# Datalogging.net
KiCad netlist of a schematic drawn in Altium Designer
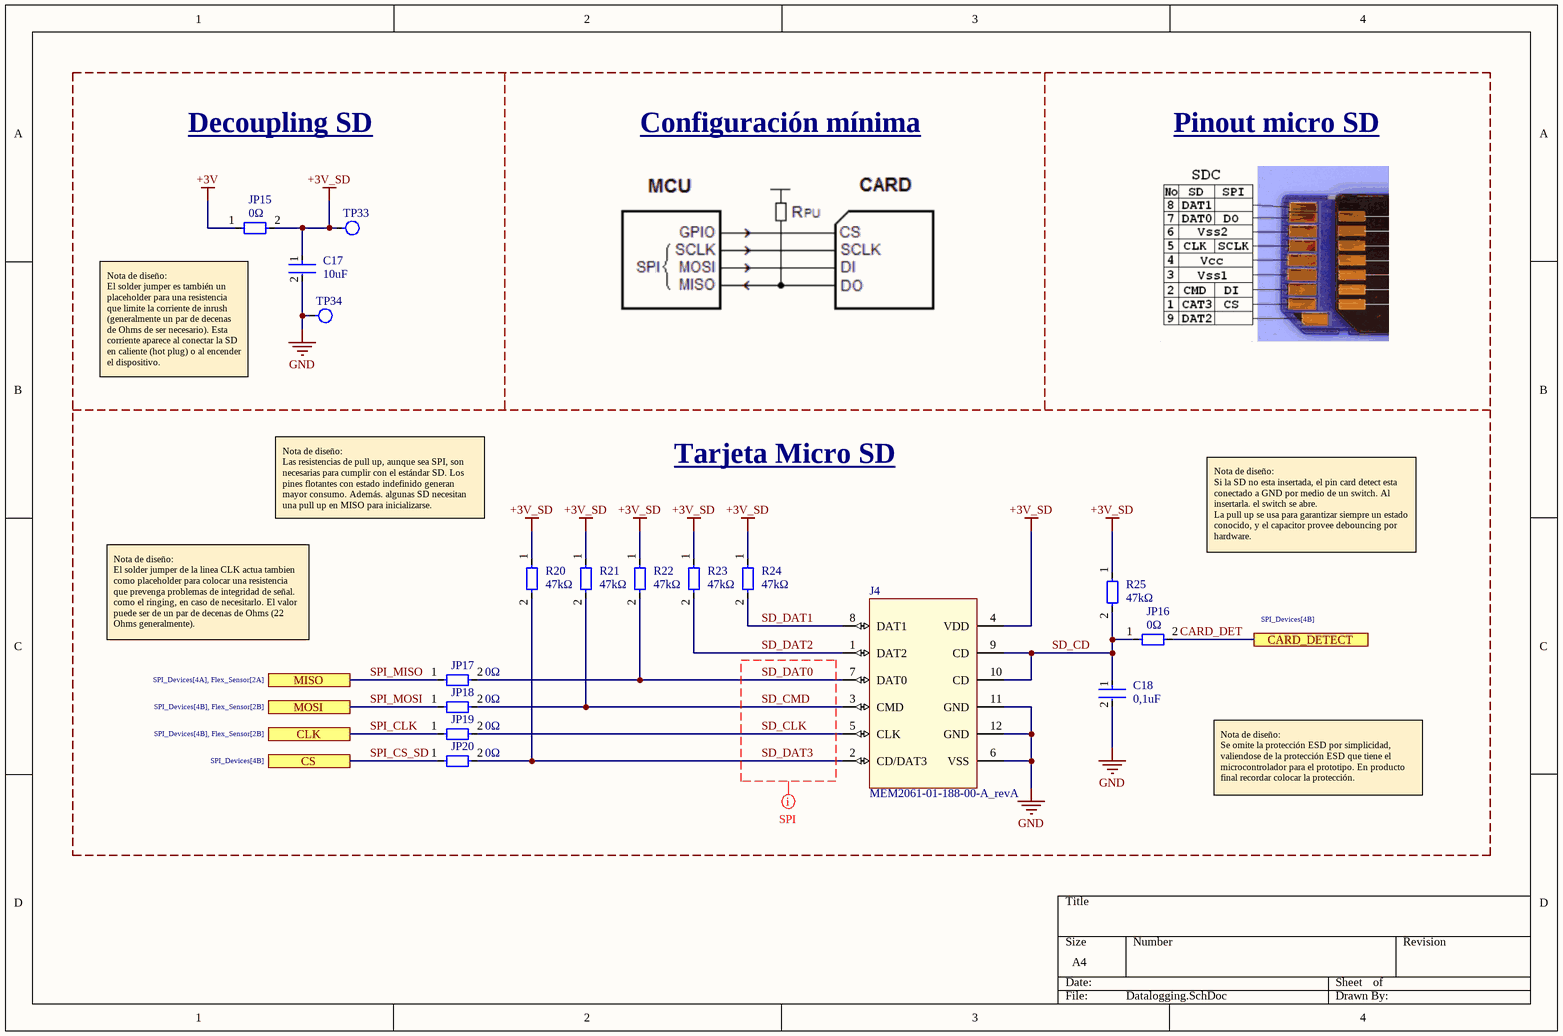
[diagram p0: Datalogging.SchDoc]

(export (version "E")
  (design (tool "Eeschema 10.0.6"))
  (components
    (comp (ref "C17")
      (value "10uF")
      (footprint "CAP_0603")
      (description "Cap 10 uF 10V X7R 0603")
      (fields (field (name "CAPACITANCE") "10uF") (field (name "TOLERANCE") "10%"))
      (libsource (lib "Passive_Components") (part "Generic C"))
    )
    (comp (ref "C18")
      (value "0.1uF")
      (footprint "CAP_0603")
      (description "Cap 0.1 uF 10V X7R 0603")
      (fields (field (name "CAPACITANCE") "0,1uF") (field (name "TOLERANCE") "10%"))
      (libsource (lib "Passive_Components") (part "Generic C"))
    )
    (comp (ref "J4")
      (value "MEM2061-01-188-00-A_revA")
      (footprint "MEM2061-01-188-00-A_revA")
      (description "Micro SD Memory Card Connector, 1.88mm Profile SMT,Push Push, with normally closed switch")
      (libsource (lib "Connectors") (part "MEM2061-01-188-00-A_revA"))
    )
    (comp (ref "JP15")
      (value "0Ω")
      (footprint "RES_0R_0603")
      (description "Simbolo de jumper genérico")
      (fields (field (name "Comment") "Generic JP"))
      (libsource (lib "Passive_Components") (part "Generic JP"))
    )
    (comp (ref "JP16")
      (value "0Ω")
      (footprint "RES_0R_0603")
      (description "Simbolo de jumper genérico")
      (fields (field (name "Comment") "Generic JP"))
      (libsource (lib "Passive_Components") (part "Generic JP"))
    )
    (comp (ref "JP17")
      (value "0Ω")
      (footprint "RES_0R_0603")
      (description "Simbolo de jumper genérico")
      (fields (field (name "Comment") "Generic JP"))
      (libsource (lib "Passive_Components") (part "Generic JP"))
    )
    (comp (ref "JP18")
      (value "0Ω")
      (footprint "RES_0R_0603")
      (description "Simbolo de jumper genérico")
      (fields (field (name "Comment") "Generic JP"))
      (libsource (lib "Passive_Components") (part "Generic JP"))
    )
    (comp (ref "JP19")
      (value "0Ω")
      (footprint "RES_0R_0603")
      (description "Simbolo de jumper genérico")
      (fields (field (name "Comment") "Generic JP"))
      (libsource (lib "Passive_Components") (part "Generic JP"))
    )
    (comp (ref "JP20")
      (value "0Ω")
      (footprint "RES_0R_0603")
      (description "Simbolo de jumper genérico")
      (fields (field (name "Comment") "Generic JP"))
      (libsource (lib "Passive_Components") (part "Generic JP"))
    )
    (comp (ref "R20")
      (value "47kΩ")
      (footprint "RES_0603")
      (description "RES  47k 1% 0603")
      (fields (field (name "Comment") "47k"))
      (libsource (lib "Passive_Components") (part "Generic R"))
    )
    (comp (ref "R21")
      (value "47kΩ")
      (footprint "RES_0603")
      (description "RES  47k 1% 0603")
      (fields (field (name "Comment") "47k"))
      (libsource (lib "Passive_Components") (part "Generic R"))
    )
    (comp (ref "R22")
      (value "47kΩ")
      (footprint "RES_0603")
      (description "RES  47k 1% 0603")
      (fields (field (name "Comment") "47k"))
      (libsource (lib "Passive_Components") (part "Generic R"))
    )
    (comp (ref "R23")
      (value "47kΩ")
      (footprint "RES_0603")
      (description "RES  47k 1% 0603")
      (fields (field (name "Comment") "47k"))
      (libsource (lib "Passive_Components") (part "Generic R"))
    )
    (comp (ref "R24")
      (value "47kΩ")
      (footprint "RES_0603")
      (description "RES  47k 1% 0603")
      (fields (field (name "Comment") "47k"))
      (libsource (lib "Passive_Components") (part "Generic R"))
    )
    (comp (ref "R25")
      (value "47kΩ")
      (footprint "RES_0603")
      (description "RES  47k 1% 0603")
      (fields (field (name "Comment") "47k"))
      (libsource (lib "Passive_Components") (part "Generic R"))
    )
    (comp (ref "TP33")
      (value "Testpoint SMD")
      (footprint "Testpoint_SMD")
      (description "Testpoint SMD de 1mm de diametro.")
      (libsource (lib "Connectors") (part "Testpoint_SMD"))
    )
    (comp (ref "TP34")
      (value "Testpoint SMD")
      (footprint "Testpoint_SMD")
      (description "Testpoint SMD de 1mm de diametro.")
      (libsource (lib "Connectors") (part "Testpoint_SMD"))
    )
  )
  (nets
    (net (code "1") (name "+3V") (class "Default")
      (node (ref "JP15") (pin "1") (pinfunction "1_1") (pintype "passive"))
    )
    (net (code "2") (name "+3V_SD") (class "Default")
      (node (ref "C17") (pin "1") (pinfunction "1_1") (pintype "passive"))
      (node (ref "J4") (pin "4") (pinfunction "VDD_4") (pintype "power_in"))
      (node (ref "JP15") (pin "2") (pinfunction "2_2") (pintype "passive"))
      (node (ref "R20") (pin "1") (pinfunction "1_1") (pintype "passive"))
      (node (ref "R21") (pin "1") (pinfunction "1_1") (pintype "passive"))
      (node (ref "R22") (pin "1") (pinfunction "1_1") (pintype "passive"))
      (node (ref "R23") (pin "1") (pinfunction "1_1") (pintype "passive"))
      (node (ref "R24") (pin "1") (pinfunction "1_1") (pintype "passive"))
      (node (ref "R25") (pin "1") (pinfunction "1_1") (pintype "passive"))
      (node (ref "TP33") (pin "1") (pinfunction "1_1") (pintype "passive"))
    )
    (net (code "3") (name "/CARD_DET") (class "Default")
      (node (ref "JP16") (pin "2") (pinfunction "2_2") (pintype "passive"))
    )
    (net (code "4") (name "/SD_CD") (class "Default")
      (node (ref "C18") (pin "1") (pinfunction "1_1") (pintype "passive"))
      (node (ref "J4") (pin "10") (pinfunction "CD_10") (pintype "passive"))
      (node (ref "J4") (pin "9") (pinfunction "CD_9") (pintype "passive"))
      (node (ref "JP16") (pin "1") (pinfunction "1_1") (pintype "passive"))
      (node (ref "R25") (pin "2") (pinfunction "2_2") (pintype "passive"))
    )
    (net (code "5") (name "/SD_CLK") (class "Default")
      (node (ref "J4") (pin "5") (pinfunction "CLK_5") (pintype "bidirectional"))
      (node (ref "JP19") (pin "2") (pinfunction "2_2") (pintype "passive"))
    )
    (net (code "6") (name "/SD_CMD") (class "Default")
      (node (ref "J4") (pin "3") (pinfunction "CMD_3") (pintype "bidirectional"))
      (node (ref "JP18") (pin "2") (pinfunction "2_2") (pintype "passive"))
      (node (ref "R21") (pin "2") (pinfunction "2_2") (pintype "passive"))
    )
    (net (code "7") (name "/SD_DAT0") (class "Default")
      (node (ref "J4") (pin "7") (pinfunction "DAT0_7") (pintype "bidirectional"))
      (node (ref "JP17") (pin "2") (pinfunction "2_2") (pintype "passive"))
      (node (ref "R22") (pin "2") (pinfunction "2_2") (pintype "passive"))
    )
    (net (code "8") (name "/SD_DAT1") (class "Default")
      (node (ref "J4") (pin "8") (pinfunction "DAT1_8") (pintype "bidirectional"))
      (node (ref "R24") (pin "2") (pinfunction "2_2") (pintype "passive"))
    )
    (net (code "9") (name "/SD_DAT2") (class "Default")
      (node (ref "J4") (pin "1") (pinfunction "DAT2_1") (pintype "bidirectional"))
      (node (ref "R23") (pin "2") (pinfunction "2_2") (pintype "passive"))
    )
    (net (code "10") (name "/SD_DAT3") (class "Default")
      (node (ref "J4") (pin "2") (pinfunction "CD/DAT3_2") (pintype "bidirectional"))
      (node (ref "JP20") (pin "2") (pinfunction "2_2") (pintype "passive"))
      (node (ref "R20") (pin "2") (pinfunction "2_2") (pintype "passive"))
    )
    (net (code "11") (name "/SPI_CLK") (class "Default")
      (node (ref "JP19") (pin "1") (pinfunction "1_1") (pintype "passive"))
    )
    (net (code "12") (name "/SPI_CS_SD") (class "Default")
      (node (ref "JP20") (pin "1") (pinfunction "1_1") (pintype "passive"))
    )
    (net (code "13") (name "/SPI_MISO") (class "Default")
      (node (ref "JP17") (pin "1") (pinfunction "1_1") (pintype "passive"))
    )
    (net (code "14") (name "/SPI_MOSI") (class "Default")
      (node (ref "JP18") (pin "1") (pinfunction "1_1") (pintype "passive"))
    )
    (net (code "15") (name "GND") (class "Default")
      (node (ref "C17") (pin "2") (pinfunction "2_2") (pintype "passive"))
      (node (ref "C18") (pin "2") (pinfunction "2_2") (pintype "passive"))
      (node (ref "J4") (pin "11") (pinfunction "GND_11") (pintype "power_in"))
      (node (ref "J4") (pin "12") (pinfunction "GND_12") (pintype "power_in"))
      (node (ref "J4") (pin "6") (pinfunction "VSS_6") (pintype "power_in"))
      (node (ref "TP34") (pin "1") (pinfunction "1_1") (pintype "passive"))
    )
  )
)
